# IR_Interface_Board.net
KiCad netlist of a schematic drawn in EAGLE
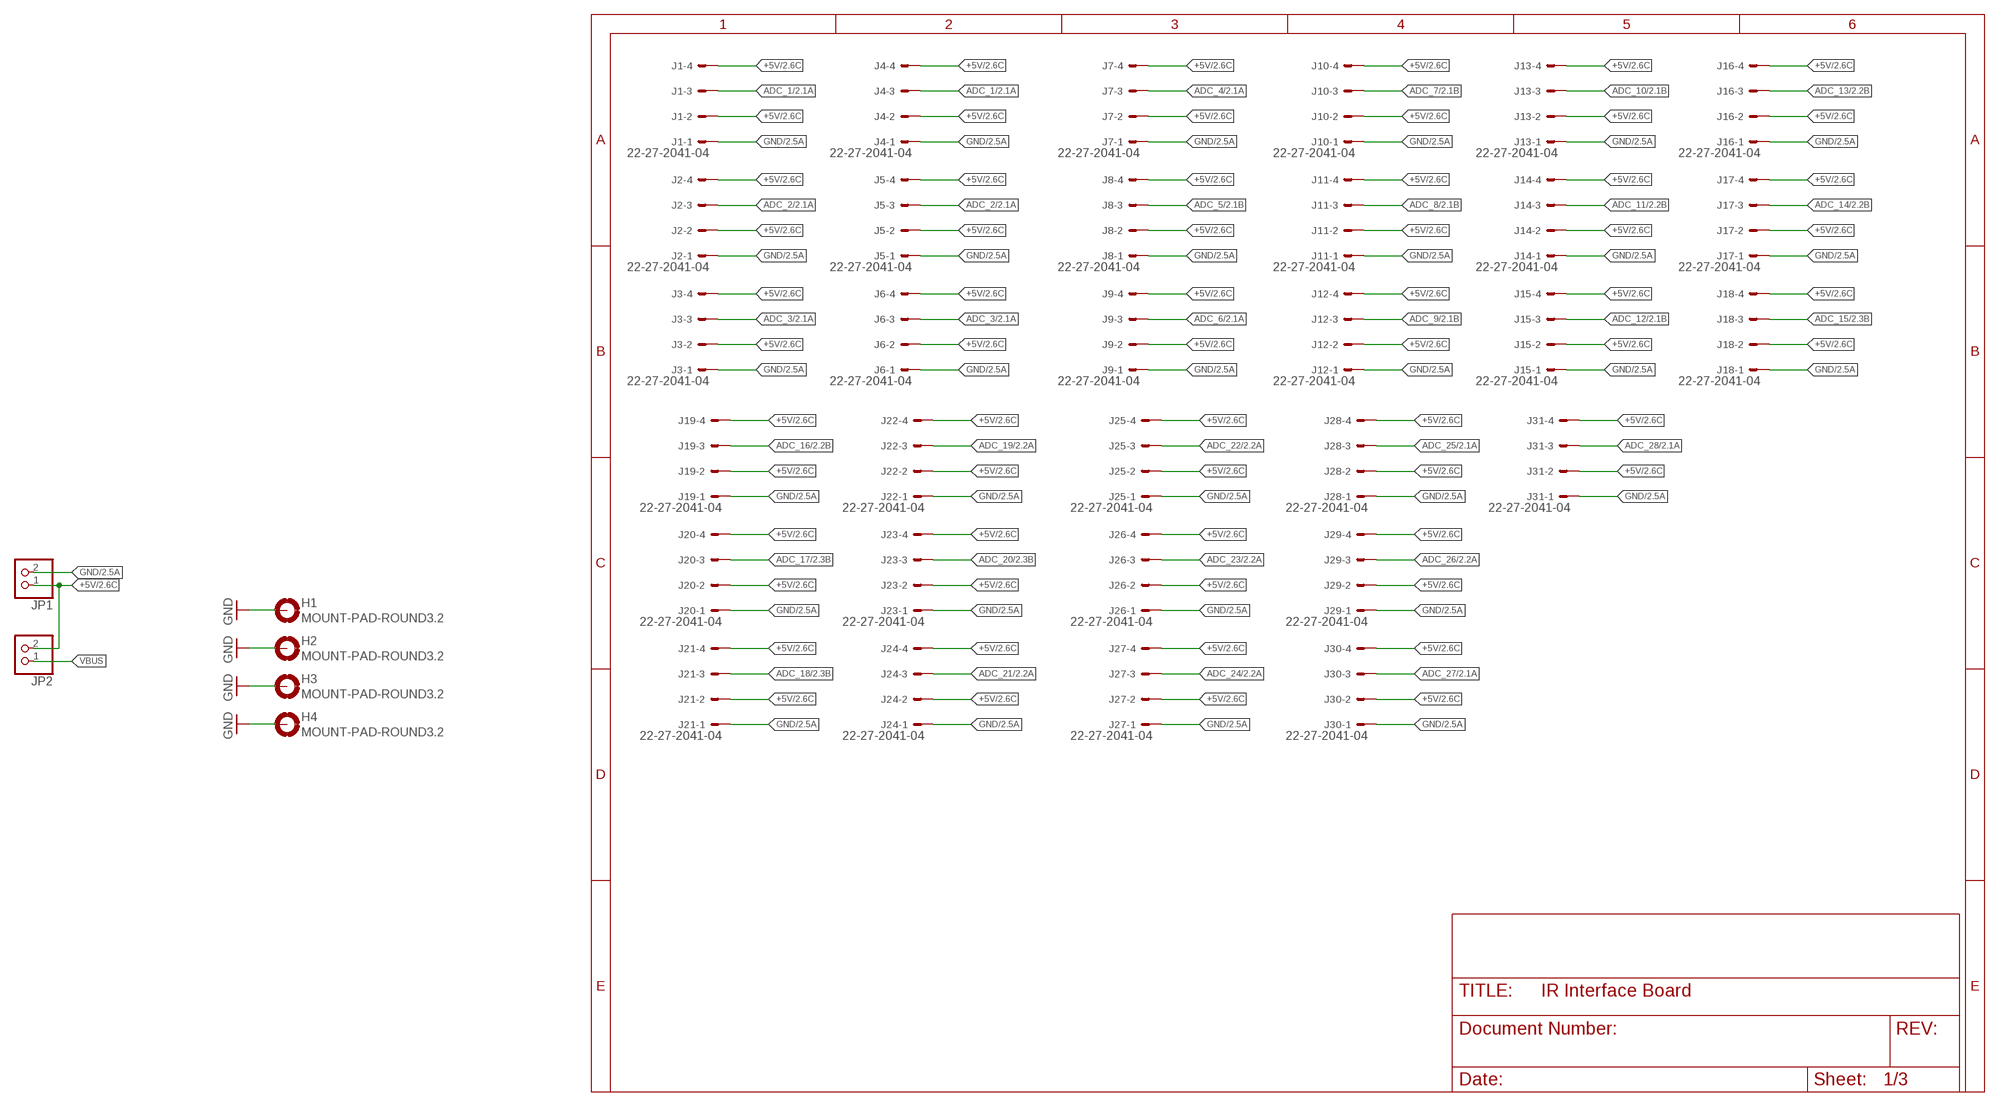
[diagram p0: schematic, sheet 1]
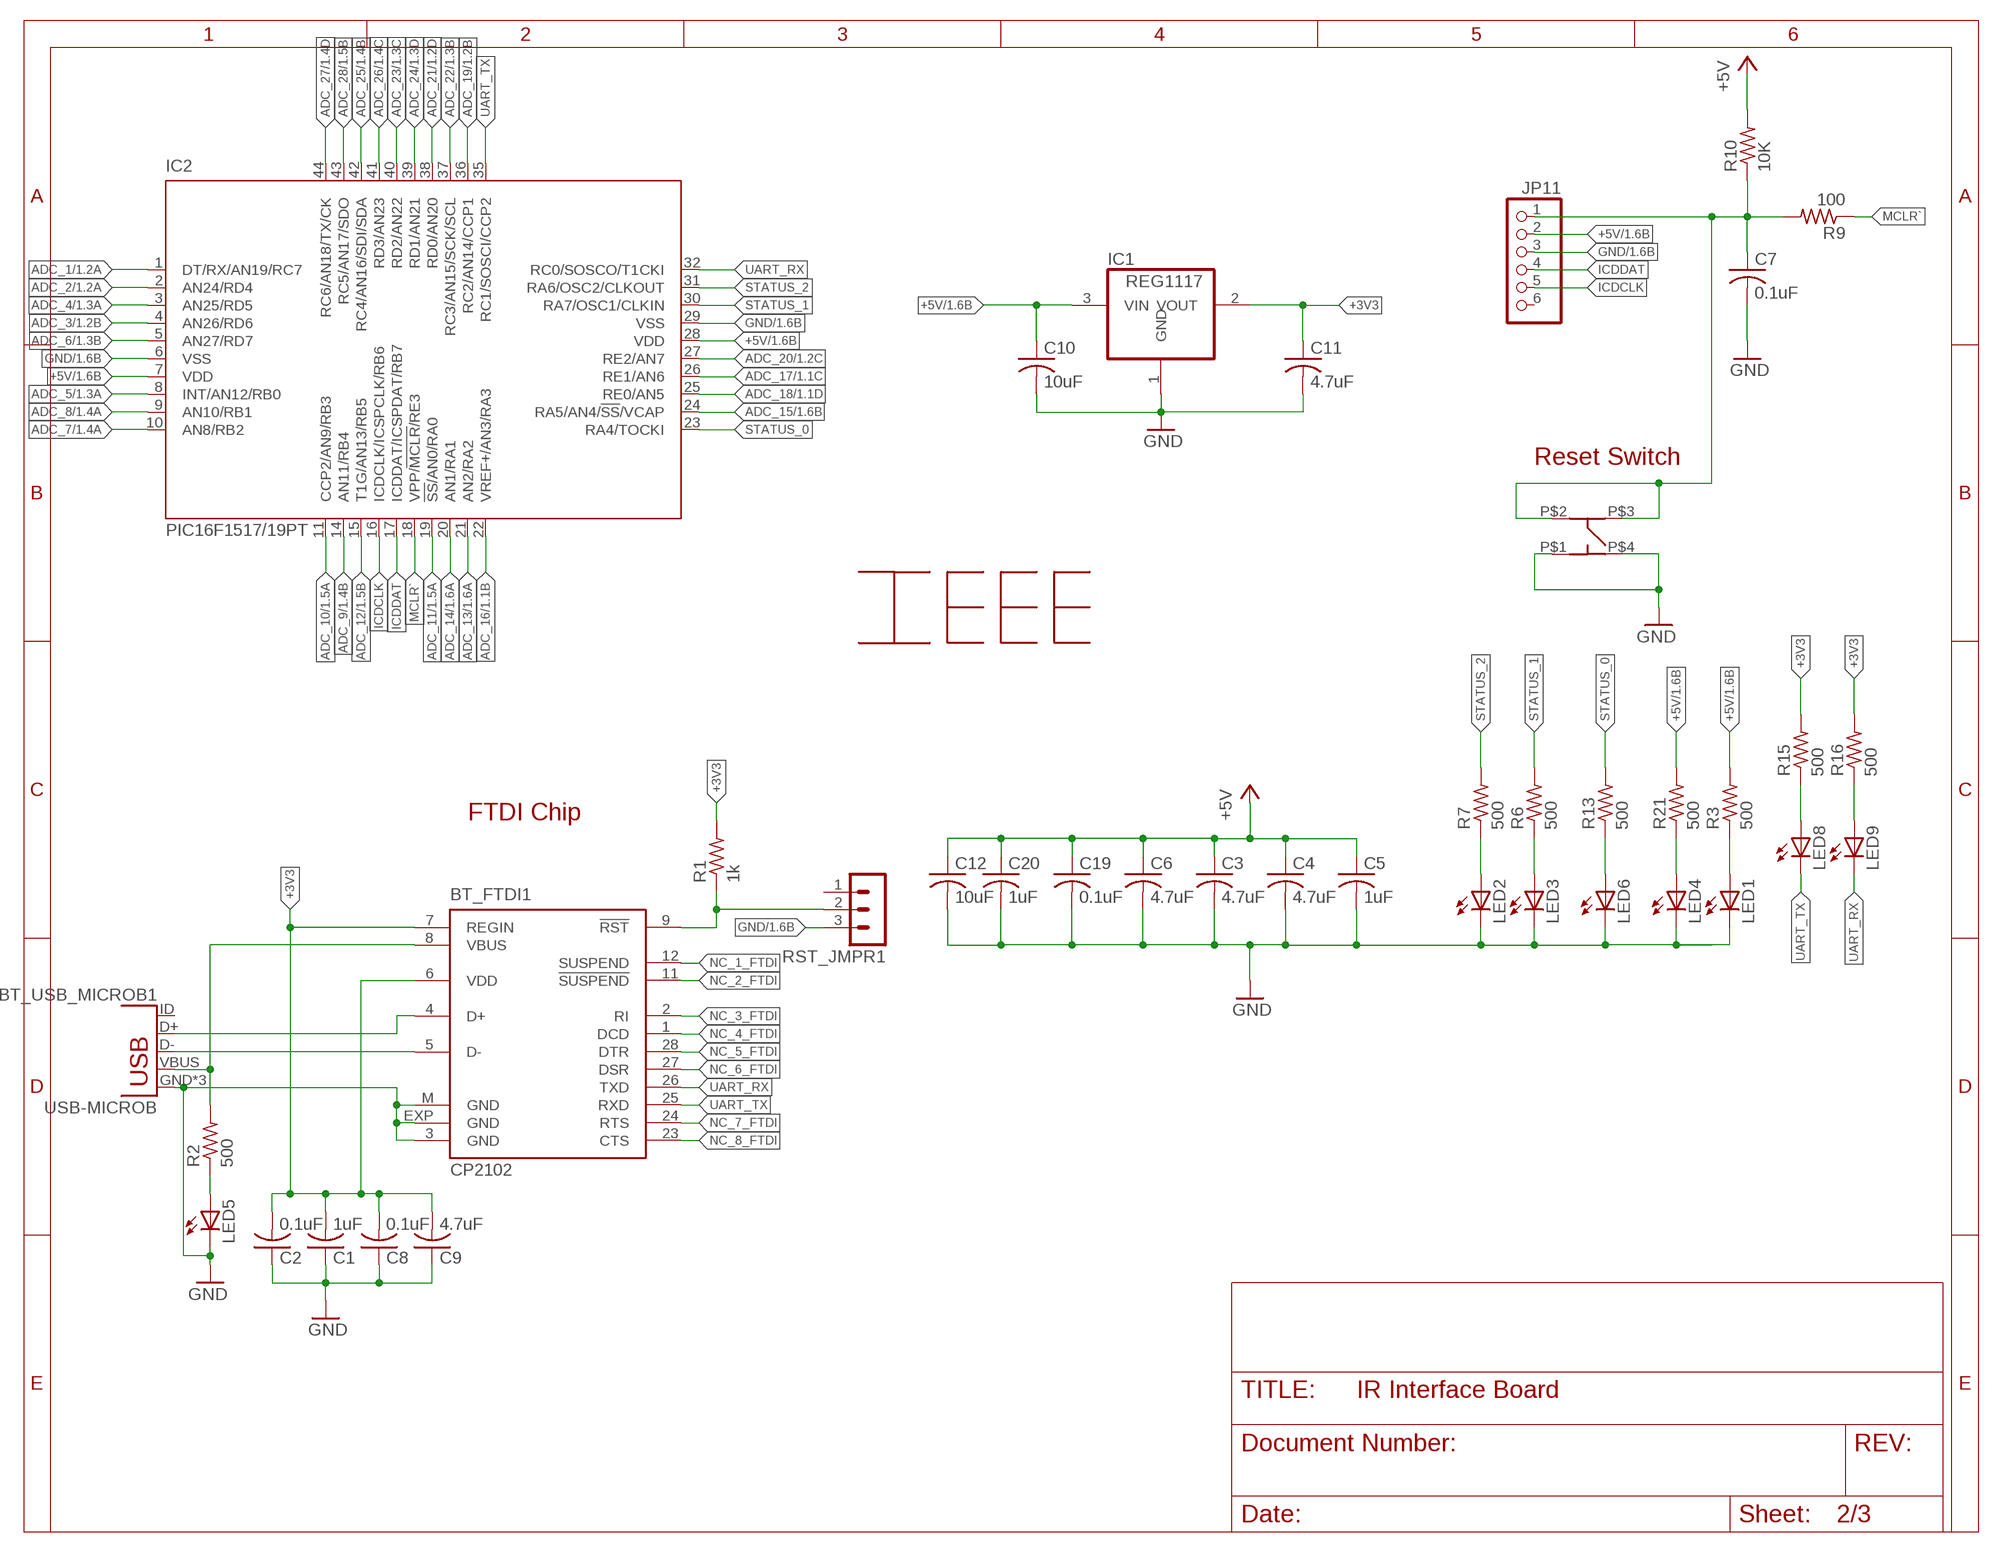
[diagram p1: schematic, sheet 2]
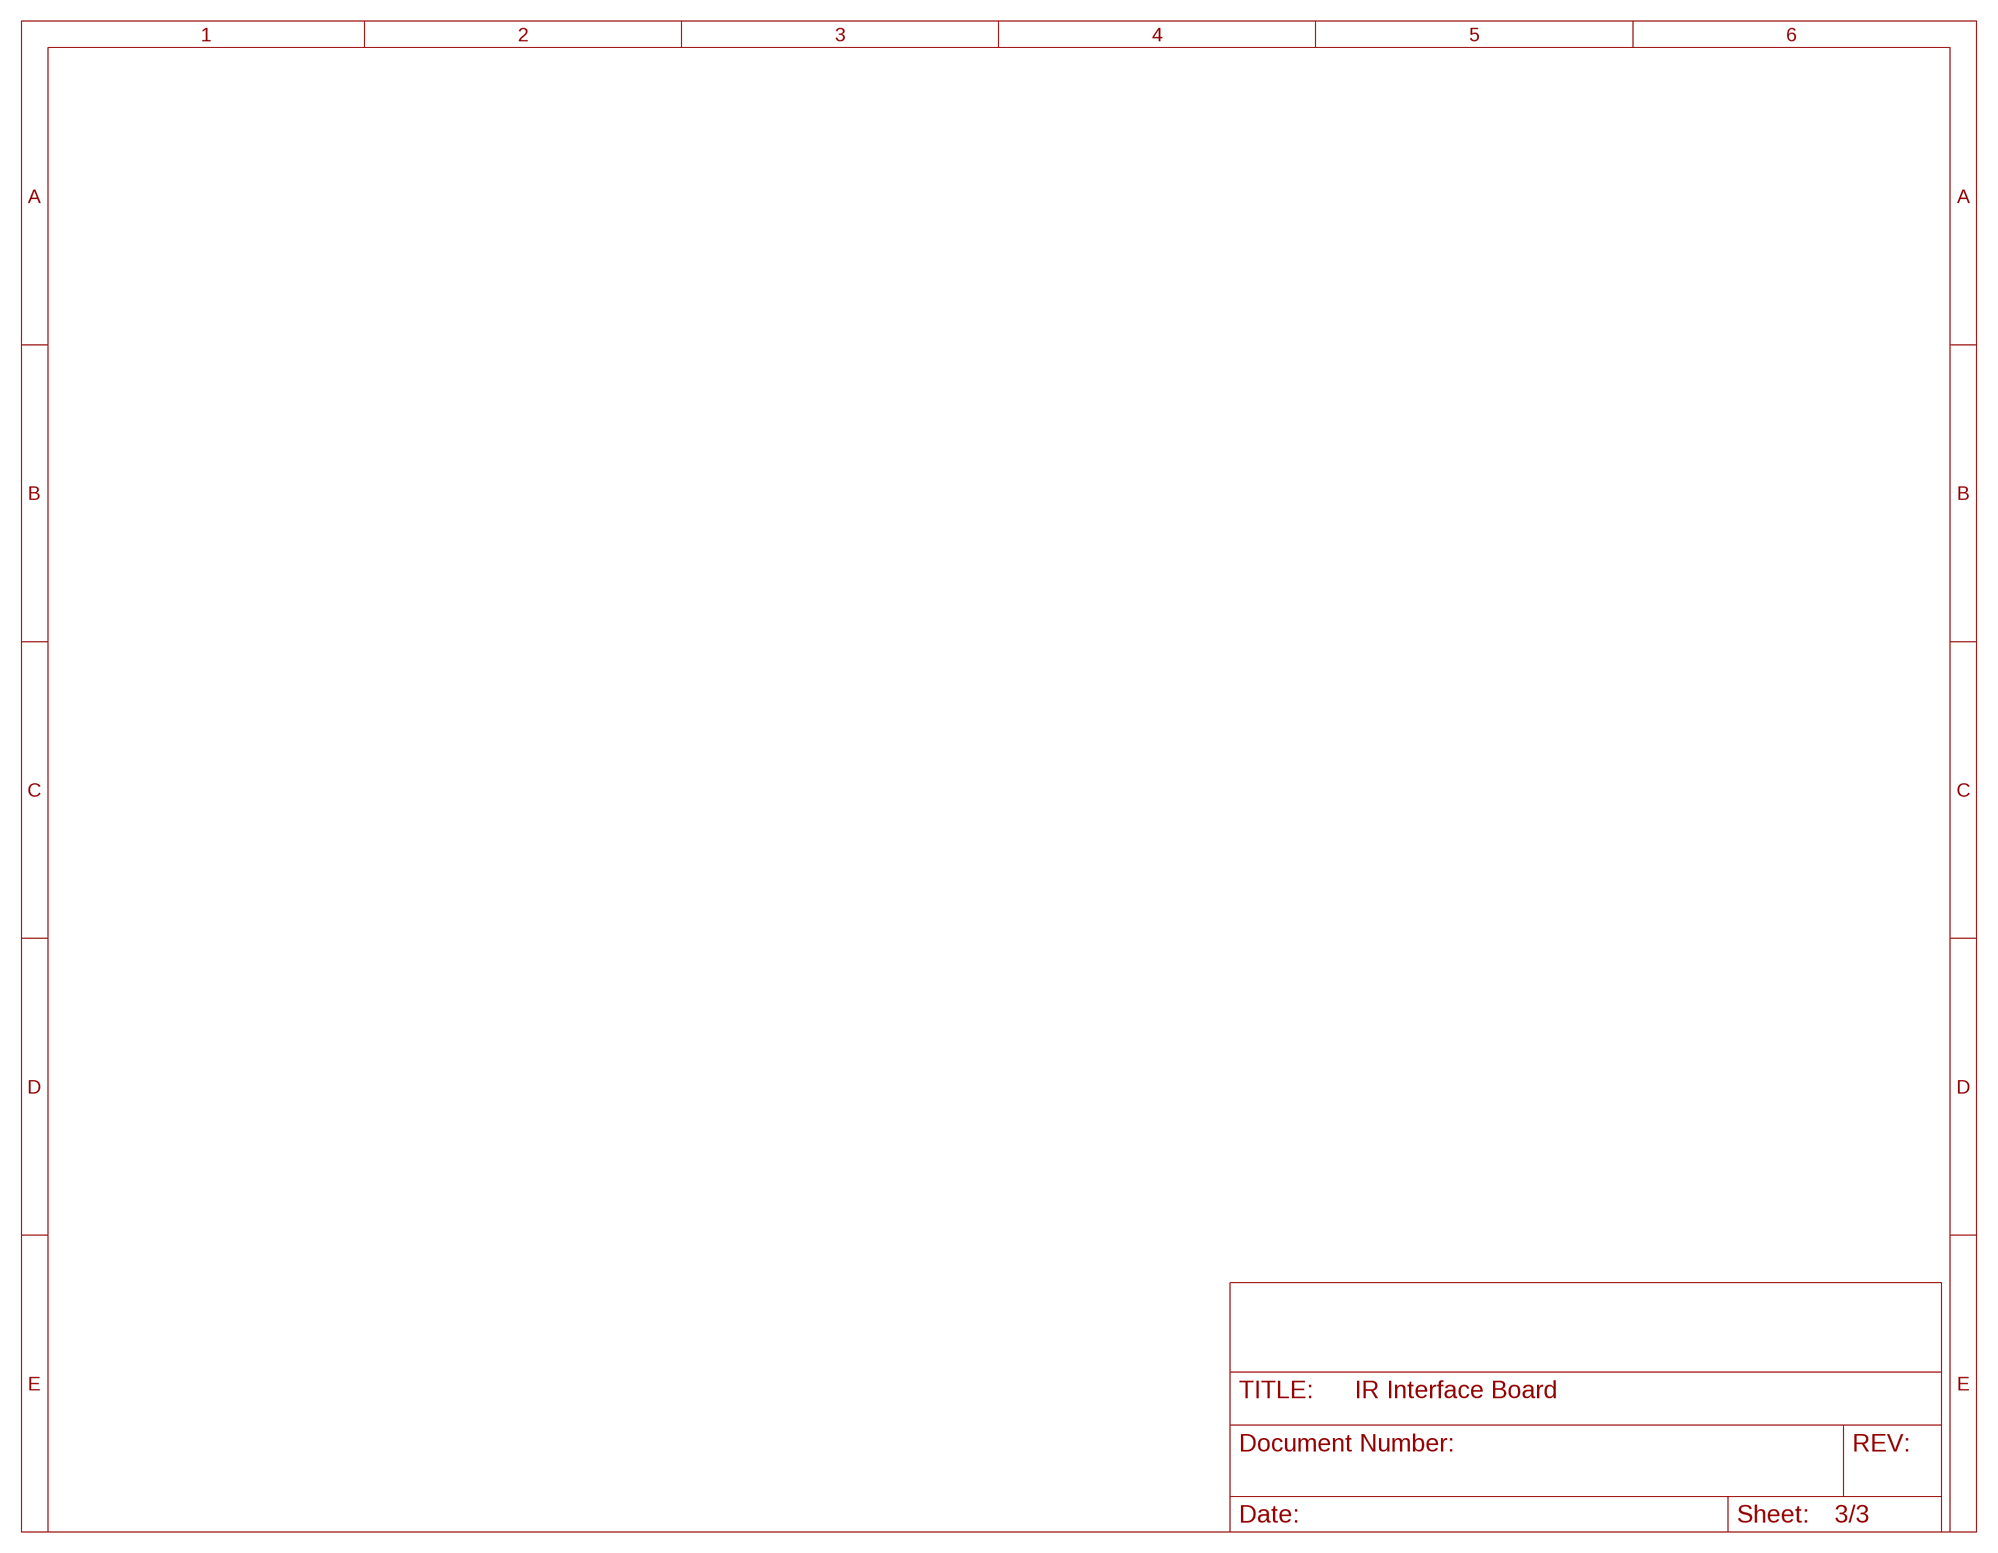
[diagram p2: schematic, sheet 3]

(export (version "E")
  (design (tool "Eeschema 10.0.6"))
  (components
    (comp (ref "BT_FTDI1")
      (value "CP2102")
      (footprint "eagle-import:MLP28")
      (fields (field (name "MF") "FARNELL") (field (name "MPN") "CP2102-GM"))
      (libsource (lib "eagle-import") (part "CP2102"))
    )
    (comp (ref "BT_USB_MICROB1")
      (value "USB-MICROB")
      (footprint "eagle-import:USB-MICROB")
      (libsource (lib "eagle-import") (part "USB-MICROB"))
    )
    (comp (ref "C1")
      (value "1uF")
      (footprint "eagle-import:C0805")
      (libsource (lib "eagle-import") (part "C-USC0805"))
    )
    (comp (ref "C2")
      (value "0.1uF")
      (footprint "eagle-import:C0805")
      (libsource (lib "eagle-import") (part "C-USC0805"))
    )
    (comp (ref "C3")
      (value "4.7uF")
      (footprint "eagle-import:C0805")
      (libsource (lib "eagle-import") (part "C-USC0805"))
    )
    (comp (ref "C4")
      (value "4.7uF")
      (footprint "eagle-import:C0805")
      (libsource (lib "eagle-import") (part "C-USC0805"))
    )
    (comp (ref "C5")
      (value "1uF")
      (footprint "eagle-import:C0805")
      (libsource (lib "eagle-import") (part "C-USC0805"))
    )
    (comp (ref "C6")
      (value "4.7uF")
      (footprint "eagle-import:C0805")
      (libsource (lib "eagle-import") (part "C-USC0805"))
    )
    (comp (ref "C7")
      (value "0.1uF")
      (footprint "eagle-import:C0805")
      (libsource (lib "eagle-import") (part "C-USC0805"))
    )
    (comp (ref "C8")
      (value "0.1uF")
      (footprint "eagle-import:C0805")
      (libsource (lib "eagle-import") (part "C-USC0805"))
    )
    (comp (ref "C9")
      (value "4.7uF")
      (footprint "eagle-import:C0805")
      (libsource (lib "eagle-import") (part "C-USC0805"))
    )
    (comp (ref "C10")
      (value "10uF")
      (footprint "eagle-import:C0805")
      (libsource (lib "eagle-import") (part "C-USC0805"))
    )
    (comp (ref "C11")
      (value "4.7uF")
      (footprint "eagle-import:C0805")
      (libsource (lib "eagle-import") (part "C-USC0805"))
    )
    (comp (ref "C12")
      (value "10uF")
      (footprint "eagle-import:C0805")
      (libsource (lib "eagle-import") (part "C-USC0805"))
    )
    (comp (ref "C19")
      (value "0.1uF")
      (footprint "eagle-import:C0805")
      (libsource (lib "eagle-import") (part "C-USC0805"))
    )
    (comp (ref "C20")
      (value "1uF")
      (footprint "eagle-import:C0805")
      (libsource (lib "eagle-import") (part "C-USC0805"))
    )
    (comp (ref "IC1")
      (value "REG1117")
      (footprint "eagle-import:SOT223")
      (libsource (lib "eagle-import") (part "REG1117"))
    )
    (comp (ref "IC2")
      (value "PIC16F1517/19PT")
      (footprint "eagle-import:TQFP44")
      (libsource (lib "eagle-import") (part "PIC16F1517/19PT"))
    )
    (comp (ref "JP11")
      (value "PINHD-1X6/90")
      (footprint "eagle-import:1X06_90")
      (libsource (lib "eagle-import") (part "PINHD-1X6/90"))
    )
    (comp (ref "LED1")
      (value "LEDSML0603")
      (footprint "eagle-import:SML0603")
      (libsource (lib "eagle-import") (part "LEDSML0603"))
    )
    (comp (ref "LED2")
      (value "LEDSML0603")
      (footprint "eagle-import:SML0603")
      (libsource (lib "eagle-import") (part "LEDSML0603"))
    )
    (comp (ref "LED3")
      (value "LEDSML0603")
      (footprint "eagle-import:SML0603")
      (libsource (lib "eagle-import") (part "LEDSML0603"))
    )
    (comp (ref "LED4")
      (value "LEDSML0603")
      (footprint "eagle-import:SML0603")
      (libsource (lib "eagle-import") (part "LEDSML0603"))
    )
    (comp (ref "LED5")
      (value "LEDSML0603")
      (footprint "eagle-import:SML0603")
      (libsource (lib "eagle-import") (part "LEDSML0603"))
    )
    (comp (ref "LED6")
      (value "LEDSML0603")
      (footprint "eagle-import:SML0603")
      (libsource (lib "eagle-import") (part "LEDSML0603"))
    )
    (comp (ref "LED8")
      (value "LEDSML0603")
      (footprint "eagle-import:SML0603")
      (libsource (lib "eagle-import") (part "LEDSML0603"))
    )
    (comp (ref "LED9")
      (value "LEDSML0603")
      (footprint "eagle-import:SML0603")
      (libsource (lib "eagle-import") (part "LEDSML0603"))
    )
    (comp (ref "R1")
      (value "1k")
      (footprint "eagle-import:R0805")
      (libsource (lib "eagle-import") (part "resistor_R-US_R0805"))
    )
    (comp (ref "R2")
      (value "500")
      (footprint "eagle-import:R0805")
      (libsource (lib "eagle-import") (part "R-US_R0805"))
    )
    (comp (ref "R3")
      (value "500")
      (footprint "eagle-import:R0805")
      (libsource (lib "eagle-import") (part "R-US_R0805"))
    )
    (comp (ref "R6")
      (value "500")
      (footprint "eagle-import:R0805")
      (libsource (lib "eagle-import") (part "R-US_R0805"))
    )
    (comp (ref "R7")
      (value "500")
      (footprint "eagle-import:R0805")
      (libsource (lib "eagle-import") (part "R-US_R0805"))
    )
    (comp (ref "R9")
      (value "100")
      (footprint "eagle-import:R0805")
      (libsource (lib "eagle-import") (part "R-US_R0805"))
    )
    (comp (ref "R10")
      (value "10K")
      (footprint "eagle-import:R0805")
      (libsource (lib "eagle-import") (part "R-US_R0805"))
    )
    (comp (ref "R13")
      (value "500")
      (footprint "eagle-import:R0805")
      (libsource (lib "eagle-import") (part "R-US_R0805"))
    )
    (comp (ref "R15")
      (value "500")
      (footprint "eagle-import:R0805")
      (libsource (lib "eagle-import") (part "R-US_R0805"))
    )
    (comp (ref "R16")
      (value "500")
      (footprint "eagle-import:R0805")
      (libsource (lib "eagle-import") (part "R-US_R0805"))
    )
    (comp (ref "R21")
      (value "500")
      (footprint "eagle-import:R0805")
      (libsource (lib "eagle-import") (part "R-US_R0805"))
    )
    (comp (ref "RST_JMPR1")
      (value "MA03-1")
      (footprint "eagle-import:MA03-1")
      (libsource (lib "eagle-import") (part "MA03-1"))
    )
    (comp (ref "TOUCH_RESET")
      (value "RESET")
      (footprint "eagle-import:MC32882_FINAL")
      (libsource (lib "eagle-import") (part "MC32882_SW"))
    )
    (comp (ref "U$1")
      (value "LOGO")
      (footprint "eagle-import:IEEE-LOGO")
      (libsource (lib "eagle-import") (part "LOGO"))
    )
    (comp (ref "H1")
      (value "MOUNT-PAD-ROUND3.2")
      (footprint "eagle-import:3,2-PAD")
      (libsource (lib "eagle-import") (part "MOUNT-PAD-ROUND3.2"))
    )
    (comp (ref "H2")
      (value "MOUNT-PAD-ROUND3.2")
      (footprint "eagle-import:3,2-PAD")
      (libsource (lib "eagle-import") (part "MOUNT-PAD-ROUND3.2"))
    )
    (comp (ref "H3")
      (value "MOUNT-PAD-ROUND3.2")
      (footprint "eagle-import:3,2-PAD")
      (libsource (lib "eagle-import") (part "MOUNT-PAD-ROUND3.2"))
    )
    (comp (ref "H4")
      (value "MOUNT-PAD-ROUND3.2")
      (footprint "eagle-import:3,2-PAD")
      (libsource (lib "eagle-import") (part "MOUNT-PAD-ROUND3.2"))
    )
    (comp (ref "J1")
      (value "22-27-2041-04")
      (footprint "eagle-import:6410-04")
      (libsource (lib "eagle-import") (part "22-?-0427-2041"))
    )
    (comp (ref "J2")
      (value "22-27-2041-04")
      (footprint "eagle-import:6410-04")
      (libsource (lib "eagle-import") (part "22-?-0427-2041"))
    )
    (comp (ref "J3")
      (value "22-27-2041-04")
      (footprint "eagle-import:6410-04")
      (libsource (lib "eagle-import") (part "22-?-0427-2041"))
    )
    (comp (ref "J4")
      (value "22-27-2041-04")
      (footprint "eagle-import:6410-04")
      (libsource (lib "eagle-import") (part "22-?-0427-2041"))
    )
    (comp (ref "J5")
      (value "22-27-2041-04")
      (footprint "eagle-import:6410-04")
      (libsource (lib "eagle-import") (part "22-?-0427-2041"))
    )
    (comp (ref "J6")
      (value "22-27-2041-04")
      (footprint "eagle-import:6410-04")
      (libsource (lib "eagle-import") (part "22-?-0427-2041"))
    )
    (comp (ref "J7")
      (value "22-27-2041-04")
      (footprint "eagle-import:6410-04")
      (libsource (lib "eagle-import") (part "22-?-0427-2041"))
    )
    (comp (ref "J8")
      (value "22-27-2041-04")
      (footprint "eagle-import:6410-04")
      (libsource (lib "eagle-import") (part "22-?-0427-2041"))
    )
    (comp (ref "J9")
      (value "22-27-2041-04")
      (footprint "eagle-import:6410-04")
      (libsource (lib "eagle-import") (part "22-?-0427-2041"))
    )
    (comp (ref "J10")
      (value "22-27-2041-04")
      (footprint "eagle-import:6410-04")
      (libsource (lib "eagle-import") (part "22-?-0427-2041"))
    )
    (comp (ref "J11")
      (value "22-27-2041-04")
      (footprint "eagle-import:6410-04")
      (libsource (lib "eagle-import") (part "22-?-0427-2041"))
    )
    (comp (ref "J12")
      (value "22-27-2041-04")
      (footprint "eagle-import:6410-04")
      (libsource (lib "eagle-import") (part "22-?-0427-2041"))
    )
    (comp (ref "J13")
      (value "22-27-2041-04")
      (footprint "eagle-import:6410-04")
      (libsource (lib "eagle-import") (part "22-?-0427-2041"))
    )
    (comp (ref "J14")
      (value "22-27-2041-04")
      (footprint "eagle-import:6410-04")
      (libsource (lib "eagle-import") (part "22-?-0427-2041"))
    )
    (comp (ref "J15")
      (value "22-27-2041-04")
      (footprint "eagle-import:6410-04")
      (libsource (lib "eagle-import") (part "22-?-0427-2041"))
    )
    (comp (ref "J16")
      (value "22-27-2041-04")
      (footprint "eagle-import:6410-04")
      (libsource (lib "eagle-import") (part "22-?-0427-2041"))
    )
    (comp (ref "J17")
      (value "22-27-2041-04")
      (footprint "eagle-import:6410-04")
      (libsource (lib "eagle-import") (part "22-?-0427-2041"))
    )
    (comp (ref "J18")
      (value "22-27-2041-04")
      (footprint "eagle-import:6410-04")
      (libsource (lib "eagle-import") (part "22-?-0427-2041"))
    )
    (comp (ref "J19")
      (value "22-27-2041-04")
      (footprint "eagle-import:6410-04")
      (libsource (lib "eagle-import") (part "22-?-0427-2041"))
    )
    (comp (ref "J20")
      (value "22-27-2041-04")
      (footprint "eagle-import:6410-04")
      (libsource (lib "eagle-import") (part "22-?-0427-2041"))
    )
    (comp (ref "J21")
      (value "22-27-2041-04")
      (footprint "eagle-import:6410-04")
      (libsource (lib "eagle-import") (part "22-?-0427-2041"))
    )
    (comp (ref "J22")
      (value "22-27-2041-04")
      (footprint "eagle-import:6410-04")
      (libsource (lib "eagle-import") (part "22-?-0427-2041"))
    )
    (comp (ref "J23")
      (value "22-27-2041-04")
      (footprint "eagle-import:6410-04")
      (libsource (lib "eagle-import") (part "22-?-0427-2041"))
    )
    (comp (ref "J24")
      (value "22-27-2041-04")
      (footprint "eagle-import:6410-04")
      (libsource (lib "eagle-import") (part "22-?-0427-2041"))
    )
    (comp (ref "J25")
      (value "22-27-2041-04")
      (footprint "eagle-import:6410-04")
      (libsource (lib "eagle-import") (part "22-?-0427-2041"))
    )
    (comp (ref "J26")
      (value "22-27-2041-04")
      (footprint "eagle-import:6410-04")
      (libsource (lib "eagle-import") (part "22-?-0427-2041"))
    )
    (comp (ref "J27")
      (value "22-27-2041-04")
      (footprint "eagle-import:6410-04")
      (libsource (lib "eagle-import") (part "22-?-0427-2041"))
    )
    (comp (ref "J28")
      (value "22-27-2041-04")
      (footprint "eagle-import:6410-04")
      (libsource (lib "eagle-import") (part "22-?-0427-2041"))
    )
    (comp (ref "J29")
      (value "22-27-2041-04")
      (footprint "eagle-import:6410-04")
      (libsource (lib "eagle-import") (part "22-?-0427-2041"))
    )
    (comp (ref "J30")
      (value "22-27-2041-04")
      (footprint "eagle-import:6410-04")
      (libsource (lib "eagle-import") (part "22-?-0427-2041"))
    )
    (comp (ref "J31")
      (value "22-27-2041-04")
      (footprint "eagle-import:6410-04")
      (libsource (lib "eagle-import") (part "22-?-0427-2041"))
    )
    (comp (ref "JP1")
      (value "PINHD-1X2")
      (footprint "eagle-import:1X02")
      (libsource (lib "eagle-import") (part "PINHD-1X2"))
    )
    (comp (ref "JP2")
      (value "PINHD-1X2")
      (footprint "eagle-import:1X02")
      (libsource (lib "eagle-import") (part "PINHD-1X2"))
    )
  )
  (nets
    (net (code "1") (name "+3V3") (class "Default")
      (node (ref "BT_FTDI1") (pin "6") (pinfunction "VDD_6") (pintype "power_in"))
      (node (ref "BT_FTDI1") (pin "7") (pinfunction "REGIN_7") (pintype "passive"))
      (node (ref "C1") (pin "2") (pinfunction "2_2") (pintype "passive"))
      (node (ref "C11") (pin "1") (pinfunction "1_1") (pintype "passive"))
      (node (ref "C2") (pin "2") (pinfunction "2_2") (pintype "passive"))
      (node (ref "C8") (pin "2") (pinfunction "2_2") (pintype "passive"))
      (node (ref "C9") (pin "2") (pinfunction "2_2") (pintype "passive"))
      (node (ref "IC1") (pin "2") (pinfunction "VOUT_2") (pintype "output"))
      (node (ref "R1") (pin "2") (pinfunction "2_2") (pintype "passive"))
      (node (ref "R15") (pin "2") (pinfunction "2_2") (pintype "passive"))
      (node (ref "R16") (pin "2") (pinfunction "2_2") (pintype "passive"))
    )
    (net (code "2") (name "+5V") (class "Default")
      (node (ref "C10") (pin "1") (pinfunction "1_1") (pintype "passive"))
      (node (ref "C12") (pin "1") (pinfunction "1_1") (pintype "passive"))
      (node (ref "C19") (pin "1") (pinfunction "1_1") (pintype "passive"))
      (node (ref "C20") (pin "1") (pinfunction "1_1") (pintype "passive"))
      (node (ref "C3") (pin "1") (pinfunction "1_1") (pintype "passive"))
      (node (ref "C4") (pin "1") (pinfunction "1_1") (pintype "passive"))
      (node (ref "C5") (pin "1") (pinfunction "1_1") (pintype "passive"))
      (node (ref "C6") (pin "1") (pinfunction "1_1") (pintype "passive"))
      (node (ref "IC1") (pin "3") (pinfunction "VIN_3") (pintype "input"))
      (node (ref "IC2") (pin "28") (pinfunction "VDD_28") (pintype "power_in"))
      (node (ref "IC2") (pin "7") (pinfunction "VDD_7") (pintype "power_in"))
      (node (ref "J1") (pin "2") (pinfunction "S_2") (pintype "passive"))
      (node (ref "J1") (pin "4") (pinfunction "S_4") (pintype "passive"))
      (node (ref "J10") (pin "2") (pinfunction "S_2") (pintype "passive"))
      (node (ref "J10") (pin "4") (pinfunction "S_4") (pintype "passive"))
      (node (ref "J11") (pin "2") (pinfunction "S_2") (pintype "passive"))
      (node (ref "J11") (pin "4") (pinfunction "S_4") (pintype "passive"))
      (node (ref "J12") (pin "2") (pinfunction "S_2") (pintype "passive"))
      (node (ref "J12") (pin "4") (pinfunction "S_4") (pintype "passive"))
      (node (ref "J13") (pin "2") (pinfunction "S_2") (pintype "passive"))
      (node (ref "J13") (pin "4") (pinfunction "S_4") (pintype "passive"))
      (node (ref "J14") (pin "2") (pinfunction "S_2") (pintype "passive"))
      (node (ref "J14") (pin "4") (pinfunction "S_4") (pintype "passive"))
      (node (ref "J15") (pin "2") (pinfunction "S_2") (pintype "passive"))
      (node (ref "J15") (pin "4") (pinfunction "S_4") (pintype "passive"))
      (node (ref "J16") (pin "2") (pinfunction "S_2") (pintype "passive"))
      (node (ref "J16") (pin "4") (pinfunction "S_4") (pintype "passive"))
      (node (ref "J17") (pin "2") (pinfunction "S_2") (pintype "passive"))
      (node (ref "J17") (pin "4") (pinfunction "S_4") (pintype "passive"))
      (node (ref "J18") (pin "2") (pinfunction "S_2") (pintype "passive"))
      (node (ref "J18") (pin "4") (pinfunction "S_4") (pintype "passive"))
      (node (ref "J19") (pin "2") (pinfunction "S_2") (pintype "passive"))
      (node (ref "J19") (pin "4") (pinfunction "S_4") (pintype "passive"))
      (node (ref "J2") (pin "2") (pinfunction "S_2") (pintype "passive"))
      (node (ref "J2") (pin "4") (pinfunction "S_4") (pintype "passive"))
      (node (ref "J20") (pin "2") (pinfunction "S_2") (pintype "passive"))
      (node (ref "J20") (pin "4") (pinfunction "S_4") (pintype "passive"))
      (node (ref "J21") (pin "2") (pinfunction "S_2") (pintype "passive"))
      (node (ref "J21") (pin "4") (pinfunction "S_4") (pintype "passive"))
      (node (ref "J22") (pin "2") (pinfunction "S_2") (pintype "passive"))
      (node (ref "J22") (pin "4") (pinfunction "S_4") (pintype "passive"))
      (node (ref "J23") (pin "2") (pinfunction "S_2") (pintype "passive"))
      (node (ref "J23") (pin "4") (pinfunction "S_4") (pintype "passive"))
      (node (ref "J24") (pin "2") (pinfunction "S_2") (pintype "passive"))
      (node (ref "J24") (pin "4") (pinfunction "S_4") (pintype "passive"))
      (node (ref "J25") (pin "2") (pinfunction "S_2") (pintype "passive"))
      (node (ref "J25") (pin "4") (pinfunction "S_4") (pintype "passive"))
      (node (ref "J26") (pin "2") (pinfunction "S_2") (pintype "passive"))
      (node (ref "J26") (pin "4") (pinfunction "S_4") (pintype "passive"))
      (node (ref "J27") (pin "2") (pinfunction "S_2") (pintype "passive"))
      (node (ref "J27") (pin "4") (pinfunction "S_4") (pintype "passive"))
      (node (ref "J28") (pin "2") (pinfunction "S_2") (pintype "passive"))
      (node (ref "J28") (pin "4") (pinfunction "S_4") (pintype "passive"))
      (node (ref "J29") (pin "2") (pinfunction "S_2") (pintype "passive"))
      (node (ref "J29") (pin "4") (pinfunction "S_4") (pintype "passive"))
      (node (ref "J3") (pin "2") (pinfunction "S_2") (pintype "passive"))
      (node (ref "J3") (pin "4") (pinfunction "S_4") (pintype "passive"))
      (node (ref "J30") (pin "2") (pinfunction "S_2") (pintype "passive"))
      (node (ref "J30") (pin "4") (pinfunction "S_4") (pintype "passive"))
      (node (ref "J31") (pin "2") (pinfunction "S_2") (pintype "passive"))
      (node (ref "J31") (pin "4") (pinfunction "S_4") (pintype "passive"))
      (node (ref "J4") (pin "2") (pinfunction "S_2") (pintype "passive"))
      (node (ref "J4") (pin "4") (pinfunction "S_4") (pintype "passive"))
      (node (ref "J5") (pin "2") (pinfunction "S_2") (pintype "passive"))
      (node (ref "J5") (pin "4") (pinfunction "S_4") (pintype "passive"))
      (node (ref "J6") (pin "2") (pinfunction "S_2") (pintype "passive"))
      (node (ref "J6") (pin "4") (pinfunction "S_4") (pintype "passive"))
      (node (ref "J7") (pin "2") (pinfunction "S_2") (pintype "passive"))
      (node (ref "J7") (pin "4") (pinfunction "S_4") (pintype "passive"))
      (node (ref "J8") (pin "2") (pinfunction "S_2") (pintype "passive"))
      (node (ref "J8") (pin "4") (pinfunction "S_4") (pintype "passive"))
      (node (ref "J9") (pin "2") (pinfunction "S_2") (pintype "passive"))
      (node (ref "J9") (pin "4") (pinfunction "S_4") (pintype "passive"))
      (node (ref "JP1") (pin "1") (pinfunction "1_1") (pintype "passive"))
      (node (ref "JP11") (pin "2") (pinfunction "2_2") (pintype "passive"))
      (node (ref "JP2") (pin "2") (pinfunction "2_2") (pintype "passive"))
      (node (ref "R10") (pin "2") (pinfunction "2_2") (pintype "passive"))
      (node (ref "R21") (pin "2") (pinfunction "2_2") (pintype "passive"))
      (node (ref "R3") (pin "2") (pinfunction "2_2") (pintype "passive"))
    )
    (net (code "3") (name "ADC_1") (class "Default")
      (node (ref "IC2") (pin "1") (pinfunction "DT/RX/AN19/RC7_1") (pintype "bidirectional"))
      (node (ref "J1") (pin "3") (pinfunction "S_3") (pintype "passive"))
      (node (ref "J4") (pin "3") (pinfunction "S_3") (pintype "passive"))
    )
    (net (code "4") (name "ADC_2") (class "Default")
      (node (ref "IC2") (pin "2") (pinfunction "AN24/RD4_2") (pintype "bidirectional"))
      (node (ref "J2") (pin "3") (pinfunction "S_3") (pintype "passive"))
      (node (ref "J5") (pin "3") (pinfunction "S_3") (pintype "passive"))
    )
    (net (code "5") (name "ADC_3") (class "Default")
      (node (ref "IC2") (pin "4") (pinfunction "AN26/RD6_4") (pintype "bidirectional"))
      (node (ref "J3") (pin "3") (pinfunction "S_3") (pintype "passive"))
      (node (ref "J6") (pin "3") (pinfunction "S_3") (pintype "passive"))
    )
    (net (code "6") (name "ADC_4") (class "Default")
      (node (ref "IC2") (pin "3") (pinfunction "AN25/RD5_3") (pintype "bidirectional"))
      (node (ref "J7") (pin "3") (pinfunction "S_3") (pintype "passive"))
    )
    (net (code "7") (name "ADC_5") (class "Default")
      (node (ref "IC2") (pin "8") (pinfunction "INT/AN12/RB0_8") (pintype "bidirectional"))
      (node (ref "J8") (pin "3") (pinfunction "S_3") (pintype "passive"))
    )
    (net (code "8") (name "ADC_6") (class "Default")
      (node (ref "IC2") (pin "5") (pinfunction "AN27/RD7_5") (pintype "bidirectional"))
      (node (ref "J9") (pin "3") (pinfunction "S_3") (pintype "passive"))
    )
    (net (code "9") (name "ADC_7") (class "Default")
      (node (ref "IC2") (pin "10") (pinfunction "AN8/RB2_10") (pintype "bidirectional"))
      (node (ref "J10") (pin "3") (pinfunction "S_3") (pintype "passive"))
    )
    (net (code "10") (name "ADC_8") (class "Default")
      (node (ref "IC2") (pin "9") (pinfunction "AN10/RB1_9") (pintype "bidirectional"))
      (node (ref "J11") (pin "3") (pinfunction "S_3") (pintype "passive"))
    )
    (net (code "11") (name "ADC_9") (class "Default")
      (node (ref "IC2") (pin "14") (pinfunction "AN11/RB4_14") (pintype "bidirectional"))
      (node (ref "J12") (pin "3") (pinfunction "S_3") (pintype "passive"))
    )
    (net (code "12") (name "ADC_10") (class "Default")
      (node (ref "IC2") (pin "11") (pinfunction "CCP2/AN9/RB3_11") (pintype "bidirectional"))
      (node (ref "J13") (pin "3") (pinfunction "S_3") (pintype "passive"))
    )
    (net (code "13") (name "ADC_11") (class "Default")
      (node (ref "IC2") (pin "19") (pinfunction "~{SS}/AN0/RA0_19") (pintype "bidirectional"))
      (node (ref "J14") (pin "3") (pinfunction "S_3") (pintype "passive"))
    )
    (net (code "14") (name "ADC_12") (class "Default")
      (node (ref "IC2") (pin "15") (pinfunction "T1G/AN13/RB5_15") (pintype "bidirectional"))
      (node (ref "J15") (pin "3") (pinfunction "S_3") (pintype "passive"))
    )
    (net (code "15") (name "ADC_13") (class "Default")
      (node (ref "IC2") (pin "21") (pinfunction "AN2/RA2_21") (pintype "bidirectional"))
      (node (ref "J16") (pin "3") (pinfunction "S_3") (pintype "passive"))
    )
    (net (code "16") (name "ADC_14") (class "Default")
      (node (ref "IC2") (pin "20") (pinfunction "AN1/RA1_20") (pintype "bidirectional"))
      (node (ref "J17") (pin "3") (pinfunction "S_3") (pintype "passive"))
    )
    (net (code "17") (name "ADC_15") (class "Default")
      (node (ref "IC2") (pin "24") (pinfunction "RA5/AN4/~{SS}/VCAP_24") (pintype "bidirectional"))
      (node (ref "J18") (pin "3") (pinfunction "S_3") (pintype "passive"))
    )
    (net (code "18") (name "ADC_16") (class "Default")
      (node (ref "IC2") (pin "22") (pinfunction "VREF+/AN3/RA3_22") (pintype "bidirectional"))
      (node (ref "J19") (pin "3") (pinfunction "S_3") (pintype "passive"))
    )
    (net (code "19") (name "ADC_17") (class "Default")
      (node (ref "IC2") (pin "26") (pinfunction "RE1/AN6_26") (pintype "bidirectional"))
      (node (ref "J20") (pin "3") (pinfunction "S_3") (pintype "passive"))
    )
    (net (code "20") (name "ADC_18") (class "Default")
      (node (ref "IC2") (pin "25") (pinfunction "RE0/AN5_25") (pintype "bidirectional"))
      (node (ref "J21") (pin "3") (pinfunction "S_3") (pintype "passive"))
    )
    (net (code "21") (name "ADC_19") (class "Default")
      (node (ref "IC2") (pin "36") (pinfunction "RC2/AN14/CCP1_36") (pintype "bidirectional"))
      (node (ref "J22") (pin "3") (pinfunction "S_3") (pintype "passive"))
    )
    (net (code "22") (name "ADC_20") (class "Default")
      (node (ref "IC2") (pin "27") (pinfunction "RE2/AN7_27") (pintype "bidirectional"))
      (node (ref "J23") (pin "3") (pinfunction "S_3") (pintype "passive"))
    )
    (net (code "23") (name "ADC_21") (class "Default")
      (node (ref "IC2") (pin "38") (pinfunction "RD0/AN20_38") (pintype "bidirectional"))
      (node (ref "J24") (pin "3") (pinfunction "S_3") (pintype "passive"))
    )
    (net (code "24") (name "ADC_22") (class "Default")
      (node (ref "IC2") (pin "37") (pinfunction "RC3/AN15/SCK/SCL_37") (pintype "bidirectional"))
      (node (ref "J25") (pin "3") (pinfunction "S_3") (pintype "passive"))
    )
    (net (code "25") (name "ADC_23") (class "Default")
      (node (ref "IC2") (pin "40") (pinfunction "RD2/AN22_40") (pintype "bidirectional"))
      (node (ref "J26") (pin "3") (pinfunction "S_3") (pintype "passive"))
    )
    (net (code "26") (name "ADC_24") (class "Default")
      (node (ref "IC2") (pin "39") (pinfunction "RD1/AN21_39") (pintype "bidirectional"))
      (node (ref "J27") (pin "3") (pinfunction "S_3") (pintype "passive"))
    )
    (net (code "27") (name "ADC_25") (class "Default")
      (node (ref "IC2") (pin "42") (pinfunction "RC4/AN16/SDI/SDA_42") (pintype "bidirectional"))
      (node (ref "J28") (pin "3") (pinfunction "S_3") (pintype "passive"))
    )
    (net (code "28") (name "ADC_26") (class "Default")
      (node (ref "IC2") (pin "41") (pinfunction "RD3/AN23_41") (pintype "bidirectional"))
      (node (ref "J29") (pin "3") (pinfunction "S_3") (pintype "passive"))
    )
    (net (code "29") (name "ADC_27") (class "Default")
      (node (ref "IC2") (pin "44") (pinfunction "RC6/AN18/TX/CK_44") (pintype "bidirectional"))
      (node (ref "J30") (pin "3") (pinfunction "S_3") (pintype "passive"))
    )
    (net (code "30") (name "ADC_28") (class "Default")
      (node (ref "IC2") (pin "43") (pinfunction "RC5/AN17/SDO_43") (pintype "bidirectional"))
      (node (ref "J31") (pin "3") (pinfunction "S_3") (pintype "passive"))
    )
    (net (code "31") (name "GND") (class "Default")
      (node (ref "BT_FTDI1") (pin "3") (pinfunction "GND_3") (pintype "power_in"))
      (node (ref "BT_FTDI1") (pin "EXP") (pinfunction "GND_EXP") (pintype "power_in"))
      (node (ref "BT_FTDI1") (pin "M") (pinfunction "GND_M") (pintype "power_in"))
      (node (ref "BT_USB_MICROB1") (pin "GND") (pinfunction "GND_GND") (pintype "bidirectional"))
      (node (ref "BT_USB_MICROB1") (pin "MT1") (pinfunction "GND_MT1") (pintype "bidirectional"))
      (node (ref "BT_USB_MICROB1") (pin "MT2") (pinfunction "GND_MT2") (pintype "bidirectional"))
      (node (ref "C1") (pin "1") (pinfunction "1_1") (pintype "passive"))
      (node (ref "C10") (pin "2") (pinfunction "2_2") (pintype "passive"))
      (node (ref "C11") (pin "2") (pinfunction "2_2") (pintype "passive"))
      (node (ref "C12") (pin "2") (pinfunction "2_2") (pintype "passive"))
      (node (ref "C19") (pin "2") (pinfunction "2_2") (pintype "passive"))
      (node (ref "C2") (pin "1") (pinfunction "1_1") (pintype "passive"))
      (node (ref "C20") (pin "2") (pinfunction "2_2") (pintype "passive"))
      (node (ref "C3") (pin "2") (pinfunction "2_2") (pintype "passive"))
      (node (ref "C4") (pin "2") (pinfunction "2_2") (pintype "passive"))
      (node (ref "C5") (pin "2") (pinfunction "2_2") (pintype "passive"))
      (node (ref "C6") (pin "2") (pinfunction "2_2") (pintype "passive"))
      (node (ref "C7") (pin "2") (pinfunction "2_2") (pintype "passive"))
      (node (ref "C8") (pin "1") (pinfunction "1_1") (pintype "passive"))
      (node (ref "C9") (pin "1") (pinfunction "1_1") (pintype "passive"))
      (node (ref "H1") (pin "B3,2") (pinfunction "MOUNT_B3,2") (pintype "passive"))
      (node (ref "H2") (pin "B3,2") (pinfunction "MOUNT_B3,2") (pintype "passive"))
      (node (ref "H3") (pin "B3,2") (pinfunction "MOUNT_B3,2") (pintype "passive"))
      (node (ref "H4") (pin "B3,2") (pinfunction "MOUNT_B3,2") (pintype "passive"))
      (node (ref "IC1") (pin "1") (pinfunction "GND_1") (pintype "power_in"))
      (node (ref "IC2") (pin "29") (pinfunction "VSS_29") (pintype "power_in"))
      (node (ref "IC2") (pin "6") (pinfunction "VSS_6") (pintype "power_in"))
      (node (ref "J1") (pin "1") (pinfunction "S_1") (pintype "passive"))
      (node (ref "J10") (pin "1") (pinfunction "S_1") (pintype "passive"))
      (node (ref "J11") (pin "1") (pinfunction "S_1") (pintype "passive"))
      (node (ref "J12") (pin "1") (pinfunction "S_1") (pintype "passive"))
      (node (ref "J13") (pin "1") (pinfunction "S_1") (pintype "passive"))
      (node (ref "J14") (pin "1") (pinfunction "S_1") (pintype "passive"))
      (node (ref "J15") (pin "1") (pinfunction "S_1") (pintype "passive"))
      (node (ref "J16") (pin "1") (pinfunction "S_1") (pintype "passive"))
      (node (ref "J17") (pin "1") (pinfunction "S_1") (pintype "passive"))
      (node (ref "J18") (pin "1") (pinfunction "S_1") (pintype "passive"))
      (node (ref "J19") (pin "1") (pinfunction "S_1") (pintype "passive"))
      (node (ref "J2") (pin "1") (pinfunction "S_1") (pintype "passive"))
      (node (ref "J20") (pin "1") (pinfunction "S_1") (pintype "passive"))
      (node (ref "J21") (pin "1") (pinfunction "S_1") (pintype "passive"))
      (node (ref "J22") (pin "1") (pinfunction "S_1") (pintype "passive"))
      (node (ref "J23") (pin "1") (pinfunction "S_1") (pintype "passive"))
      (node (ref "J24") (pin "1") (pinfunction "S_1") (pintype "passive"))
      (node (ref "J25") (pin "1") (pinfunction "S_1") (pintype "passive"))
      (node (ref "J26") (pin "1") (pinfunction "S_1") (pintype "passive"))
      (node (ref "J27") (pin "1") (pinfunction "S_1") (pintype "passive"))
      (node (ref "J28") (pin "1") (pinfunction "S_1") (pintype "passive"))
      (node (ref "J29") (pin "1") (pinfunction "S_1") (pintype "passive"))
      (node (ref "J3") (pin "1") (pinfunction "S_1") (pintype "passive"))
      (node (ref "J30") (pin "1") (pinfunction "S_1") (pintype "passive"))
      (node (ref "J31") (pin "1") (pinfunction "S_1") (pintype "passive"))
      (node (ref "J4") (pin "1") (pinfunction "S_1") (pintype "passive"))
      (node (ref "J5") (pin "1") (pinfunction "S_1") (pintype "passive"))
      (node (ref "J6") (pin "1") (pinfunction "S_1") (pintype "passive"))
      (node (ref "J7") (pin "1") (pinfunction "S_1") (pintype "passive"))
      (node (ref "J8") (pin "1") (pinfunction "S_1") (pintype "passive"))
      (node (ref "J9") (pin "1") (pinfunction "S_1") (pintype "passive"))
      (node (ref "JP1") (pin "2") (pinfunction "2_2") (pintype "passive"))
      (node (ref "JP11") (pin "3") (pinfunction "3_3") (pintype "passive"))
      (node (ref "LED1") (pin "C") (pinfunction "C_C") (pintype "passive"))
      (node (ref "LED2") (pin "C") (pinfunction "C_C") (pintype "passive"))
      (node (ref "LED3") (pin "C") (pinfunction "C_C") (pintype "passive"))
      (node (ref "LED4") (pin "C") (pinfunction "C_C") (pintype "passive"))
      (node (ref "LED5") (pin "C") (pinfunction "C_C") (pintype "passive"))
      (node (ref "LED6") (pin "C") (pinfunction "C_C") (pintype "passive"))
      (node (ref "RST_JMPR1") (pin "3") (pinfunction "3_3") (pintype "passive"))
      (node (ref "TOUCH_RESET") (pin "P$1") (pinfunction "P1_P$1") (pintype "bidirectional"))
      (node (ref "TOUCH_RESET") (pin "P$4") (pinfunction "P4_P$4") (pintype "bidirectional"))
    )
    (net (code "32") (name "ICDCLK") (class "Default")
      (node (ref "IC2") (pin "16") (pinfunction "ICDCLK/ICSPCLK/RB6_16") (pintype "bidirectional"))
      (node (ref "JP11") (pin "5") (pinfunction "5_5") (pintype "passive"))
    )
    (net (code "33") (name "ICDDAT") (class "Default")
      (node (ref "IC2") (pin "17") (pinfunction "ICDDAT/ICSPDAT/RB7_17") (pintype "bidirectional"))
      (node (ref "JP11") (pin "4") (pinfunction "4_4") (pintype "passive"))
    )
    (net (code "34") (name "MCLR`") (class "Default")
      (node (ref "IC2") (pin "18") (pinfunction "VPP/~{MCLR}/RE3_18") (pintype "input"))
      (node (ref "R9") (pin "1") (pinfunction "1_1") (pintype "passive"))
    )
    (net (code "35") (name "NC_1_FTDI") (class "Default")
      (node (ref "BT_FTDI1") (pin "12") (pinfunction "SUSPEND_12") (pintype "output"))
    )
    (net (code "36") (name "NC_2_FTDI") (class "Default")
      (node (ref "BT_FTDI1") (pin "11") (pinfunction "~{SUSPEND}_11") (pintype "output"))
    )
    (net (code "37") (name "NC_3_FTDI") (class "Default")
      (node (ref "BT_FTDI1") (pin "2") (pinfunction "RI_2") (pintype "input"))
    )
    (net (code "38") (name "NC_4_FTDI") (class "Default")
      (node (ref "BT_FTDI1") (pin "1") (pinfunction "DCD_1") (pintype "input"))
    )
    (net (code "39") (name "NC_5_FTDI") (class "Default")
      (node (ref "BT_FTDI1") (pin "28") (pinfunction "DTR_28") (pintype "output"))
    )
    (net (code "40") (name "NC_6_FTDI") (class "Default")
      (node (ref "BT_FTDI1") (pin "27") (pinfunction "DSR_27") (pintype "input"))
    )
    (net (code "41") (name "NC_7_FTDI") (class "Default")
      (node (ref "BT_FTDI1") (pin "24") (pinfunction "RTS_24") (pintype "output"))
    )
    (net (code "42") (name "NC_8_FTDI") (class "Default")
      (node (ref "BT_FTDI1") (pin "23") (pinfunction "CTS_23") (pintype "input"))
    )
    (net (code "43") (name "Net-(BT_FTDI1-D+)") (class "Default")
      (node (ref "BT_FTDI1") (pin "4") (pinfunction "D+_4") (pintype "bidirectional"))
      (node (ref "BT_USB_MICROB1") (pin "D+") (pinfunction "D+_D+") (pintype "bidirectional"))
    )
    (net (code "44") (name "Net-(BT_FTDI1-D-)") (class "Default")
      (node (ref "BT_FTDI1") (pin "5") (pinfunction "D-_5") (pintype "bidirectional"))
      (node (ref "BT_USB_MICROB1") (pin "D-") (pinfunction "D-_D-") (pintype "bidirectional"))
    )
    (net (code "45") (name "Net-(BT_FTDI1-~{RST})") (class "Default")
      (node (ref "BT_FTDI1") (pin "9") (pinfunction "~{RST}_9") (pintype "bidirectional"))
      (node (ref "R1") (pin "1") (pinfunction "1_1") (pintype "passive"))
      (node (ref "RST_JMPR1") (pin "2") (pinfunction "2_2") (pintype "passive"))
    )
    (net (code "46") (name "Net-(LED1-PadA)") (class "Default")
      (node (ref "LED1") (pin "A") (pinfunction "A_A") (pintype "passive"))
      (node (ref "R3") (pin "1") (pinfunction "1_1") (pintype "passive"))
    )
    (net (code "47") (name "Net-(LED2-PadA)") (class "Default")
      (node (ref "LED2") (pin "A") (pinfunction "A_A") (pintype "passive"))
      (node (ref "R7") (pin "1") (pinfunction "1_1") (pintype "passive"))
    )
    (net (code "48") (name "Net-(LED3-PadA)") (class "Default")
      (node (ref "LED3") (pin "A") (pinfunction "A_A") (pintype "passive"))
      (node (ref "R6") (pin "1") (pinfunction "1_1") (pintype "passive"))
    )
    (net (code "49") (name "Net-(LED4-PadA)") (class "Default")
      (node (ref "LED4") (pin "A") (pinfunction "A_A") (pintype "passive"))
      (node (ref "R21") (pin "1") (pinfunction "1_1") (pintype "passive"))
    )
    (net (code "50") (name "Net-(LED5-PadA)") (class "Default")
      (node (ref "LED5") (pin "A") (pinfunction "A_A") (pintype "passive"))
      (node (ref "R2") (pin "1") (pinfunction "1_1") (pintype "passive"))
    )
    (net (code "51") (name "Net-(LED6-PadA)") (class "Default")
      (node (ref "LED6") (pin "A") (pinfunction "A_A") (pintype "passive"))
      (node (ref "R13") (pin "1") (pinfunction "1_1") (pintype "passive"))
    )
    (net (code "52") (name "Net-(LED8-PadA)") (class "Default")
      (node (ref "LED8") (pin "A") (pinfunction "A_A") (pintype "passive"))
      (node (ref "R15") (pin "1") (pinfunction "1_1") (pintype "passive"))
    )
    (net (code "53") (name "Net-(LED9-PadA)") (class "Default")
      (node (ref "LED9") (pin "A") (pinfunction "A_A") (pintype "passive"))
      (node (ref "R16") (pin "1") (pinfunction "1_1") (pintype "passive"))
    )
    (net (code "54") (name "Net-(TOUCH_RESET-P2)") (class "Default")
      (node (ref "C7") (pin "1") (pinfunction "1_1") (pintype "passive"))
      (node (ref "JP11") (pin "1") (pinfunction "1_1") (pintype "passive"))
      (node (ref "R10") (pin "1") (pinfunction "1_1") (pintype "passive"))
      (node (ref "R9") (pin "2") (pinfunction "2_2") (pintype "passive"))
      (node (ref "TOUCH_RESET") (pin "P$2") (pinfunction "P2_P$2") (pintype "bidirectional"))
      (node (ref "TOUCH_RESET") (pin "P$3") (pinfunction "P3_P$3") (pintype "bidirectional"))
    )
    (net (code "55") (name "STATUS_0") (class "Default")
      (node (ref "IC2") (pin "23") (pinfunction "RA4/TOCKI_23") (pintype "bidirectional"))
      (node (ref "R13") (pin "2") (pinfunction "2_2") (pintype "passive"))
    )
    (net (code "56") (name "STATUS_1") (class "Default")
      (node (ref "IC2") (pin "30") (pinfunction "RA7/OSC1/CLKIN_30") (pintype "bidirectional"))
      (node (ref "R6") (pin "2") (pinfunction "2_2") (pintype "passive"))
    )
    (net (code "57") (name "STATUS_2") (class "Default")
      (node (ref "IC2") (pin "31") (pinfunction "RA6/OSC2/CLKOUT_31") (pintype "bidirectional"))
      (node (ref "R7") (pin "2") (pinfunction "2_2") (pintype "passive"))
    )
    (net (code "58") (name "UART_RX") (class "Default")
      (node (ref "BT_FTDI1") (pin "26") (pinfunction "TXD_26") (pintype "output"))
      (node (ref "IC2") (pin "32") (pinfunction "RC0/SOSCO/T1CKI_32") (pintype "bidirectional"))
      (node (ref "LED9") (pin "C") (pinfunction "C_C") (pintype "passive"))
    )
    (net (code "59") (name "UART_TX") (class "Default")
      (node (ref "BT_FTDI1") (pin "25") (pinfunction "RXD_25") (pintype "input"))
      (node (ref "IC2") (pin "35") (pinfunction "RC1/SOSCI/CCP2_35") (pintype "bidirectional"))
      (node (ref "LED8") (pin "C") (pinfunction "C_C") (pintype "passive"))
    )
    (net (code "60") (name "VBUS") (class "Default")
      (node (ref "BT_FTDI1") (pin "8") (pinfunction "VBUS_8") (pintype "input"))
      (node (ref "BT_USB_MICROB1") (pin "VBUS") (pinfunction "VBUS_VBUS") (pintype "bidirectional"))
      (node (ref "JP2") (pin "1") (pinfunction "1_1") (pintype "passive"))
      (node (ref "R2") (pin "2") (pinfunction "2_2") (pintype "passive"))
    )
    (net (code "61") (name "unconnected-(BT_USB_MICROB1-PadID)") (class "Default")
      (node (ref "BT_USB_MICROB1") (pin "ID") (pinfunction "ID_ID") (pintype "bidirectional"))
    )
    (net (code "62") (name "unconnected-(JP11-Pad6)") (class "Default")
      (node (ref "JP11") (pin "6") (pinfunction "6_6") (pintype "passive"))
    )
    (net (code "63") (name "unconnected-(RST_JMPR1-Pad1)") (class "Default")
      (node (ref "RST_JMPR1") (pin "1") (pinfunction "1_1") (pintype "passive"))
    )
  )
)
